# 2ModuleBoard.net
KiCad netlist of a schematic drawn in EAGLE
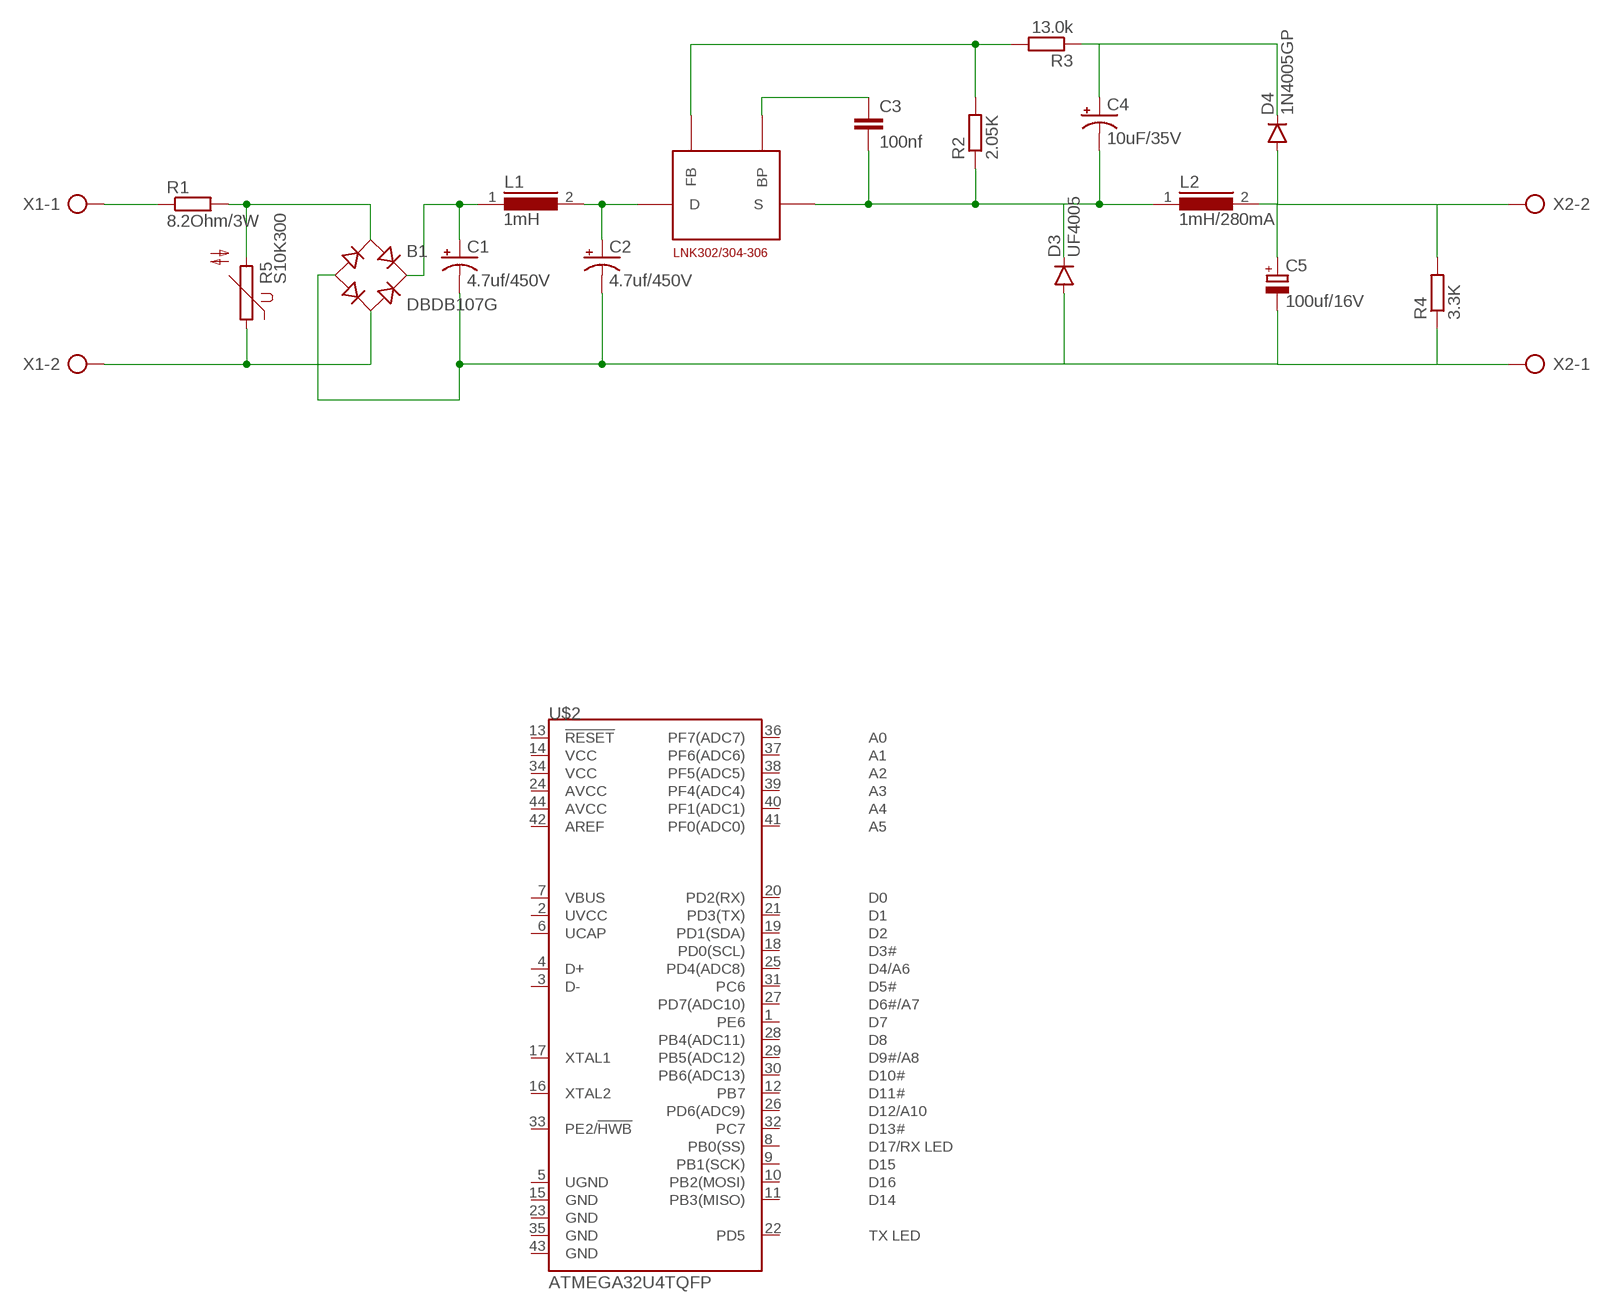
[diagram p0: schematic, sheet 1]

(export (version "E")
  (design (tool "Eeschema 10.0.6"))
  (components
    (comp (ref "B1")
      (value "DBDB107G")
      (footprint "eagle-import:DB")
      (libsource (lib "eagle-import") (part "DB?GDB107"))
    )
    (comp (ref "C1")
      (value "4.7uf/450V")
      (footprint "eagle-import:CPOL-RADIAL-1000UF-25V-KIT")
      (libsource (lib "eagle-import") (part "1000UF-25V(PTH)KIT"))
    )
    (comp (ref "C2")
      (value "4.7uf/450V")
      (footprint "eagle-import:CPOL-RADIAL-1000UF-25V-KIT")
      (libsource (lib "eagle-import") (part "1000UF-25V(PTH)KIT"))
    )
    (comp (ref "C3")
      (value "100nf")
      (footprint "eagle-import:C2.5-4")
      (libsource (lib "eagle-import") (part "C2.5/4"))
    )
    (comp (ref "C4")
      (value "10uF/35V")
      (footprint "eagle-import:EIA3216")
      (libsource (lib "eagle-import") (part "10UF-TANT"))
    )
    (comp (ref "C5")
      (value "100uf/16V")
      (footprint "eagle-import:E2,5-7")
      (libsource (lib "eagle-import") (part "CPOL-EUE2.5-7"))
    )
    (comp (ref "D3")
      (value "UF4005")
      (footprint "eagle-import:DIODE-1N4148-KIT")
      (libsource (lib "eagle-import") (part "DIODEKIT"))
    )
    (comp (ref "D4")
      (value "1N4005GP")
      (footprint "eagle-import:DIODE-1N4148-KIT")
      (libsource (lib "eagle-import") (part "DIODEKIT"))
    )
    (comp (ref "L1")
      (value "1mH")
      (footprint "eagle-import:82114R")
      (libsource (lib "eagle-import") (part "82114R"))
    )
    (comp (ref "L2")
      (value "1mH/280mA")
      (footprint "eagle-import:82114R")
      (libsource (lib "eagle-import") (part "82114R"))
    )
    (comp (ref "R1")
      (value "8.2Ohm/3W")
      (footprint "eagle-import:0411_15")
      (libsource (lib "eagle-import") (part "R-EU_0411/15"))
    )
    (comp (ref "R2")
      (value "2.05K")
      (footprint "eagle-import:M1206")
      (libsource (lib "eagle-import") (part "R-EU_M1206"))
    )
    (comp (ref "R3")
      (value "13.0k")
      (footprint "eagle-import:M1206")
      (libsource (lib "eagle-import") (part "R-EU_M1206"))
    )
    (comp (ref "R4")
      (value "3.3K")
      (footprint "eagle-import:M1206")
      (libsource (lib "eagle-import") (part "R-EU_M1206"))
    )
    (comp (ref "R5")
      (value "S10K300")
      (footprint "eagle-import:S10K300")
      (libsource (lib "eagle-import") (part "S10K300"))
    )
    (comp (ref "U$1")
      (value "LNK302/304-306")
      (footprint "eagle-import:SMD-8B")
      (libsource (lib "eagle-import") (part "LNK302/304-306"))
    )
    (comp (ref "U$2")
      (value "ATMEGA32U4TQFP")
      (footprint "eagle-import:SPARKFUN-DIGITALIC_TQFP44")
      (libsource (lib "eagle-import") (part "ATMEGA32U4TQFP"))
    )
    (comp (ref "X1")
      (value "AK300/2")
      (footprint "eagle-import:AK300_2")
      (libsource (lib "eagle-import") (part "AK300/2"))
    )
    (comp (ref "X2")
      (value "AK300/2")
      (footprint "eagle-import:AK300_2")
      (libsource (lib "eagle-import") (part "AK300/2"))
    )
  )
  (nets
    (net (code "1") (name "Net-(B1-Pad+)") (class "Default")
      (node (ref "B1") (pin "+") (pinfunction "+_+") (pintype "passive"))
      (node (ref "C1") (pin "+") (pinfunction "+_+") (pintype "passive"))
      (node (ref "L1") (pin "1") (pinfunction "1_1") (pintype "passive"))
    )
    (net (code "2") (name "Net-(B1-PadAC1)") (class "Default")
      (node (ref "B1") (pin "AC1") (pinfunction "AC1_AC1") (pintype "passive"))
      (node (ref "R1") (pin "2") (pinfunction "2_2") (pintype "passive"))
      (node (ref "R5") (pin "2") (pinfunction "2_2") (pintype "passive"))
    )
    (net (code "3") (name "Net-(C2-Pad+)") (class "Default")
      (node (ref "C2") (pin "+") (pinfunction "+_+") (pintype "passive"))
      (node (ref "L1") (pin "2") (pinfunction "2_2") (pintype "passive"))
      (node (ref "U$1") (pin "D") (pinfunction "D_D") (pintype "bidirectional"))
    )
    (net (code "4") (name "Net-(C3-Pad1)") (class "Default")
      (node (ref "C3") (pin "1") (pinfunction "1_1") (pintype "passive"))
      (node (ref "U$1") (pin "BP") (pinfunction "BP_BP") (pintype "bidirectional"))
    )
    (net (code "5") (name "Net-(C4-+)") (class "Default")
      (node (ref "C4") (pin "A") (pinfunction "+_A") (pintype "passive"))
      (node (ref "D4") (pin "C") (pinfunction "C_C") (pintype "passive"))
      (node (ref "R3") (pin "1") (pinfunction "1_1") (pintype "passive"))
    )
    (net (code "6") (name "Net-(C4--)") (class "Default")
      (node (ref "C3") (pin "2") (pinfunction "2_2") (pintype "passive"))
      (node (ref "C4") (pin "C") (pinfunction "-_C") (pintype "passive"))
      (node (ref "D3") (pin "C") (pinfunction "C_C") (pintype "passive"))
      (node (ref "L2") (pin "1") (pinfunction "1_1") (pintype "passive"))
      (node (ref "R2") (pin "1") (pinfunction "1_1") (pintype "passive"))
      (node (ref "U$1") (pin "S1") (pinfunction "S_S1") (pintype "bidirectional"))
    )
    (net (code "7") (name "Net-(R2-Pad2)") (class "Default")
      (node (ref "R2") (pin "2") (pinfunction "2_2") (pintype "passive"))
      (node (ref "R3") (pin "2") (pinfunction "2_2") (pintype "passive"))
      (node (ref "U$1") (pin "FB") (pinfunction "FB_FB") (pintype "bidirectional"))
    )
    (net (code "8") (name "Net-(X1A-KL)") (class "Default")
      (node (ref "R1") (pin "1") (pinfunction "1_1") (pintype "passive"))
      (node (ref "X1") (pin "1") (pinfunction "KL_1") (pintype "passive"))
    )
    (net (code "9") (name "Net-(X1B-KL)") (class "Default")
      (node (ref "B1") (pin "AC2") (pinfunction "AC2_AC2") (pintype "passive"))
      (node (ref "R5") (pin "1") (pinfunction "1_1") (pintype "passive"))
      (node (ref "X1") (pin "2") (pinfunction "KL_2") (pintype "passive"))
    )
    (net (code "10") (name "Net-(X2A-KL)") (class "Default")
      (node (ref "B1") (pin "-") (pinfunction "-_-") (pintype "passive"))
      (node (ref "C1") (pin "-") (pinfunction "-_-") (pintype "passive"))
      (node (ref "C2") (pin "-") (pinfunction "-_-") (pintype "passive"))
      (node (ref "C5") (pin "-") (pinfunction "-_-") (pintype "passive"))
      (node (ref "D3") (pin "A") (pinfunction "A_A") (pintype "passive"))
      (node (ref "R4") (pin "1") (pinfunction "1_1") (pintype "passive"))
      (node (ref "X2") (pin "1") (pinfunction "KL_1") (pintype "passive"))
    )
    (net (code "11") (name "Net-(X2B-KL)") (class "Default")
      (node (ref "C5") (pin "+") (pinfunction "+_+") (pintype "passive"))
      (node (ref "D4") (pin "A") (pinfunction "A_A") (pintype "passive"))
      (node (ref "L2") (pin "2") (pinfunction "2_2") (pintype "passive"))
      (node (ref "R4") (pin "2") (pinfunction "2_2") (pintype "passive"))
      (node (ref "X2") (pin "2") (pinfunction "KL_2") (pintype "passive"))
    )
    (net (code "12") (name "unconnected-(U$2-AREF-Pad42)") (class "Default")
      (node (ref "U$2") (pin "42") (pinfunction "AREF_42") (pintype "bidirectional"))
    )
    (net (code "13") (name "unconnected-(U$2-AVCC-Pad24)") (class "Default")
      (node (ref "U$2") (pin "24") (pinfunction "AVCC_24") (pintype "bidirectional"))
    )
    (net (code "14") (name "unconnected-(U$2-AVCC-Pad44)") (class "Default")
      (node (ref "U$2") (pin "44") (pinfunction "AVCC_44") (pintype "bidirectional"))
    )
    (net (code "15") (name "unconnected-(U$2-D+-Pad4)") (class "Default")
      (node (ref "U$2") (pin "4") (pinfunction "D+_4") (pintype "bidirectional"))
    )
    (net (code "16") (name "unconnected-(U$2-D--Pad3)") (class "Default")
      (node (ref "U$2") (pin "3") (pinfunction "D-_3") (pintype "bidirectional"))
    )
    (net (code "17") (name "unconnected-(U$2-GND-Pad15)") (class "Default")
      (node (ref "U$2") (pin "15") (pinfunction "GND_15") (pintype "bidirectional"))
    )
    (net (code "18") (name "unconnected-(U$2-GND-Pad23)") (class "Default")
      (node (ref "U$2") (pin "23") (pinfunction "GND_23") (pintype "bidirectional"))
    )
    (net (code "19") (name "unconnected-(U$2-GND-Pad35)") (class "Default")
      (node (ref "U$2") (pin "35") (pinfunction "GND_35") (pintype "bidirectional"))
    )
    (net (code "20") (name "unconnected-(U$2-GND-Pad43)") (class "Default")
      (node (ref "U$2") (pin "43") (pinfunction "GND_43") (pintype "bidirectional"))
    )
    (net (code "21") (name "unconnected-(U$2-PB0(SS)-Pad8)") (class "Default")
      (node (ref "U$2") (pin "8") (pinfunction "PB0(SS)_8") (pintype "bidirectional"))
    )
    (net (code "22") (name "unconnected-(U$2-PB1(SCK)-Pad9)") (class "Default")
      (node (ref "U$2") (pin "9") (pinfunction "PB1(SCK)_9") (pintype "bidirectional"))
    )
    (net (code "23") (name "unconnected-(U$2-PB2(MOSI)-Pad10)") (class "Default")
      (node (ref "U$2") (pin "10") (pinfunction "PB2(MOSI)_10") (pintype "bidirectional"))
    )
    (net (code "24") (name "unconnected-(U$2-PB3(MISO)-Pad11)") (class "Default")
      (node (ref "U$2") (pin "11") (pinfunction "PB3(MISO)_11") (pintype "bidirectional"))
    )
    (net (code "25") (name "unconnected-(U$2-PB4(ADC11)-Pad28)") (class "Default")
      (node (ref "U$2") (pin "28") (pinfunction "PB4(ADC11)_28") (pintype "bidirectional"))
    )
    (net (code "26") (name "unconnected-(U$2-PB5(ADC12)-Pad29)") (class "Default")
      (node (ref "U$2") (pin "29") (pinfunction "PB5(ADC12)_29") (pintype "bidirectional"))
    )
    (net (code "27") (name "unconnected-(U$2-PB6(ADC13)-Pad30)") (class "Default")
      (node (ref "U$2") (pin "30") (pinfunction "PB6(ADC13)_30") (pintype "bidirectional"))
    )
    (net (code "28") (name "unconnected-(U$2-PB7-Pad12)") (class "Default")
      (node (ref "U$2") (pin "12") (pinfunction "PB7_12") (pintype "bidirectional"))
    )
    (net (code "29") (name "unconnected-(U$2-PC6-Pad31)") (class "Default")
      (node (ref "U$2") (pin "31") (pinfunction "PC6_31") (pintype "bidirectional"))
    )
    (net (code "30") (name "unconnected-(U$2-PC7-Pad32)") (class "Default")
      (node (ref "U$2") (pin "32") (pinfunction "PC7_32") (pintype "bidirectional"))
    )
    (net (code "31") (name "unconnected-(U$2-PD0(SCL)-Pad18)") (class "Default")
      (node (ref "U$2") (pin "18") (pinfunction "PD0(SCL)_18") (pintype "bidirectional"))
    )
    (net (code "32") (name "unconnected-(U$2-PD1(SDA)-Pad19)") (class "Default")
      (node (ref "U$2") (pin "19") (pinfunction "PD1(SDA)_19") (pintype "bidirectional"))
    )
    (net (code "33") (name "unconnected-(U$2-PD2(RX)-Pad20)") (class "Default")
      (node (ref "U$2") (pin "20") (pinfunction "PD2(RX)_20") (pintype "bidirectional"))
    )
    (net (code "34") (name "unconnected-(U$2-PD3(TX)-Pad21)") (class "Default")
      (node (ref "U$2") (pin "21") (pinfunction "PD3(TX)_21") (pintype "bidirectional"))
    )
    (net (code "35") (name "unconnected-(U$2-PD4(ADC8)-Pad25)") (class "Default")
      (node (ref "U$2") (pin "25") (pinfunction "PD4(ADC8)_25") (pintype "bidirectional"))
    )
    (net (code "36") (name "unconnected-(U$2-PD5-Pad22)") (class "Default")
      (node (ref "U$2") (pin "22") (pinfunction "PD5_22") (pintype "bidirectional"))
    )
    (net (code "37") (name "unconnected-(U$2-PD6(ADC9)-Pad26)") (class "Default")
      (node (ref "U$2") (pin "26") (pinfunction "PD6(ADC9)_26") (pintype "bidirectional"))
    )
    (net (code "38") (name "unconnected-(U$2-PD7(ADC10)-Pad27)") (class "Default")
      (node (ref "U$2") (pin "27") (pinfunction "PD7(ADC10)_27") (pintype "bidirectional"))
    )
    (net (code "39") (name "unconnected-(U$2-PE2{slash}~{HWB}-Pad33)") (class "Default")
      (node (ref "U$2") (pin "33") (pinfunction "PE2/~{HWB}_33") (pintype "bidirectional"))
    )
    (net (code "40") (name "unconnected-(U$2-PE6-Pad1)") (class "Default")
      (node (ref "U$2") (pin "1") (pinfunction "PE6_1") (pintype "bidirectional"))
    )
    (net (code "41") (name "unconnected-(U$2-PF0(ADC0)-Pad41)") (class "Default")
      (node (ref "U$2") (pin "41") (pinfunction "PF0(ADC0)_41") (pintype "bidirectional"))
    )
    (net (code "42") (name "unconnected-(U$2-PF1(ADC1)-Pad40)") (class "Default")
      (node (ref "U$2") (pin "40") (pinfunction "PF1(ADC1)_40") (pintype "bidirectional"))
    )
    (net (code "43") (name "unconnected-(U$2-PF4(ADC4)-Pad39)") (class "Default")
      (node (ref "U$2") (pin "39") (pinfunction "PF4(ADC4)_39") (pintype "bidirectional"))
    )
    (net (code "44") (name "unconnected-(U$2-PF5(ADC5)-Pad38)") (class "Default")
      (node (ref "U$2") (pin "38") (pinfunction "PF5(ADC5)_38") (pintype "bidirectional"))
    )
    (net (code "45") (name "unconnected-(U$2-PF6(ADC6)-Pad37)") (class "Default")
      (node (ref "U$2") (pin "37") (pinfunction "PF6(ADC6)_37") (pintype "bidirectional"))
    )
    (net (code "46") (name "unconnected-(U$2-PF7(ADC7)-Pad36)") (class "Default")
      (node (ref "U$2") (pin "36") (pinfunction "PF7(ADC7)_36") (pintype "bidirectional"))
    )
    (net (code "47") (name "unconnected-(U$2-UCAP-Pad6)") (class "Default")
      (node (ref "U$2") (pin "6") (pinfunction "UCAP_6") (pintype "bidirectional"))
    )
    (net (code "48") (name "unconnected-(U$2-UGND-Pad5)") (class "Default")
      (node (ref "U$2") (pin "5") (pinfunction "UGND_5") (pintype "bidirectional"))
    )
    (net (code "49") (name "unconnected-(U$2-UVCC-Pad2)") (class "Default")
      (node (ref "U$2") (pin "2") (pinfunction "UVCC_2") (pintype "bidirectional"))
    )
    (net (code "50") (name "unconnected-(U$2-VBUS-Pad7)") (class "Default")
      (node (ref "U$2") (pin "7") (pinfunction "VBUS_7") (pintype "bidirectional"))
    )
    (net (code "51") (name "unconnected-(U$2-VCC-Pad14)") (class "Default")
      (node (ref "U$2") (pin "14") (pinfunction "VCC_14") (pintype "bidirectional"))
    )
    (net (code "52") (name "unconnected-(U$2-VCC-Pad34)") (class "Default")
      (node (ref "U$2") (pin "34") (pinfunction "VCC_34") (pintype "bidirectional"))
    )
    (net (code "53") (name "unconnected-(U$2-XTAL1-Pad17)") (class "Default")
      (node (ref "U$2") (pin "17") (pinfunction "XTAL1_17") (pintype "bidirectional"))
    )
    (net (code "54") (name "unconnected-(U$2-XTAL2-Pad16)") (class "Default")
      (node (ref "U$2") (pin "16") (pinfunction "XTAL2_16") (pintype "bidirectional"))
    )
    (net (code "55") (name "unconnected-(U$2-~{RESET}-Pad13)") (class "Default")
      (node (ref "U$2") (pin "13") (pinfunction "~{RESET}_13") (pintype "bidirectional"))
    )
  )
)
